# flash.net
KiCad netlist of a schematic drawn in EasyEDA Pro
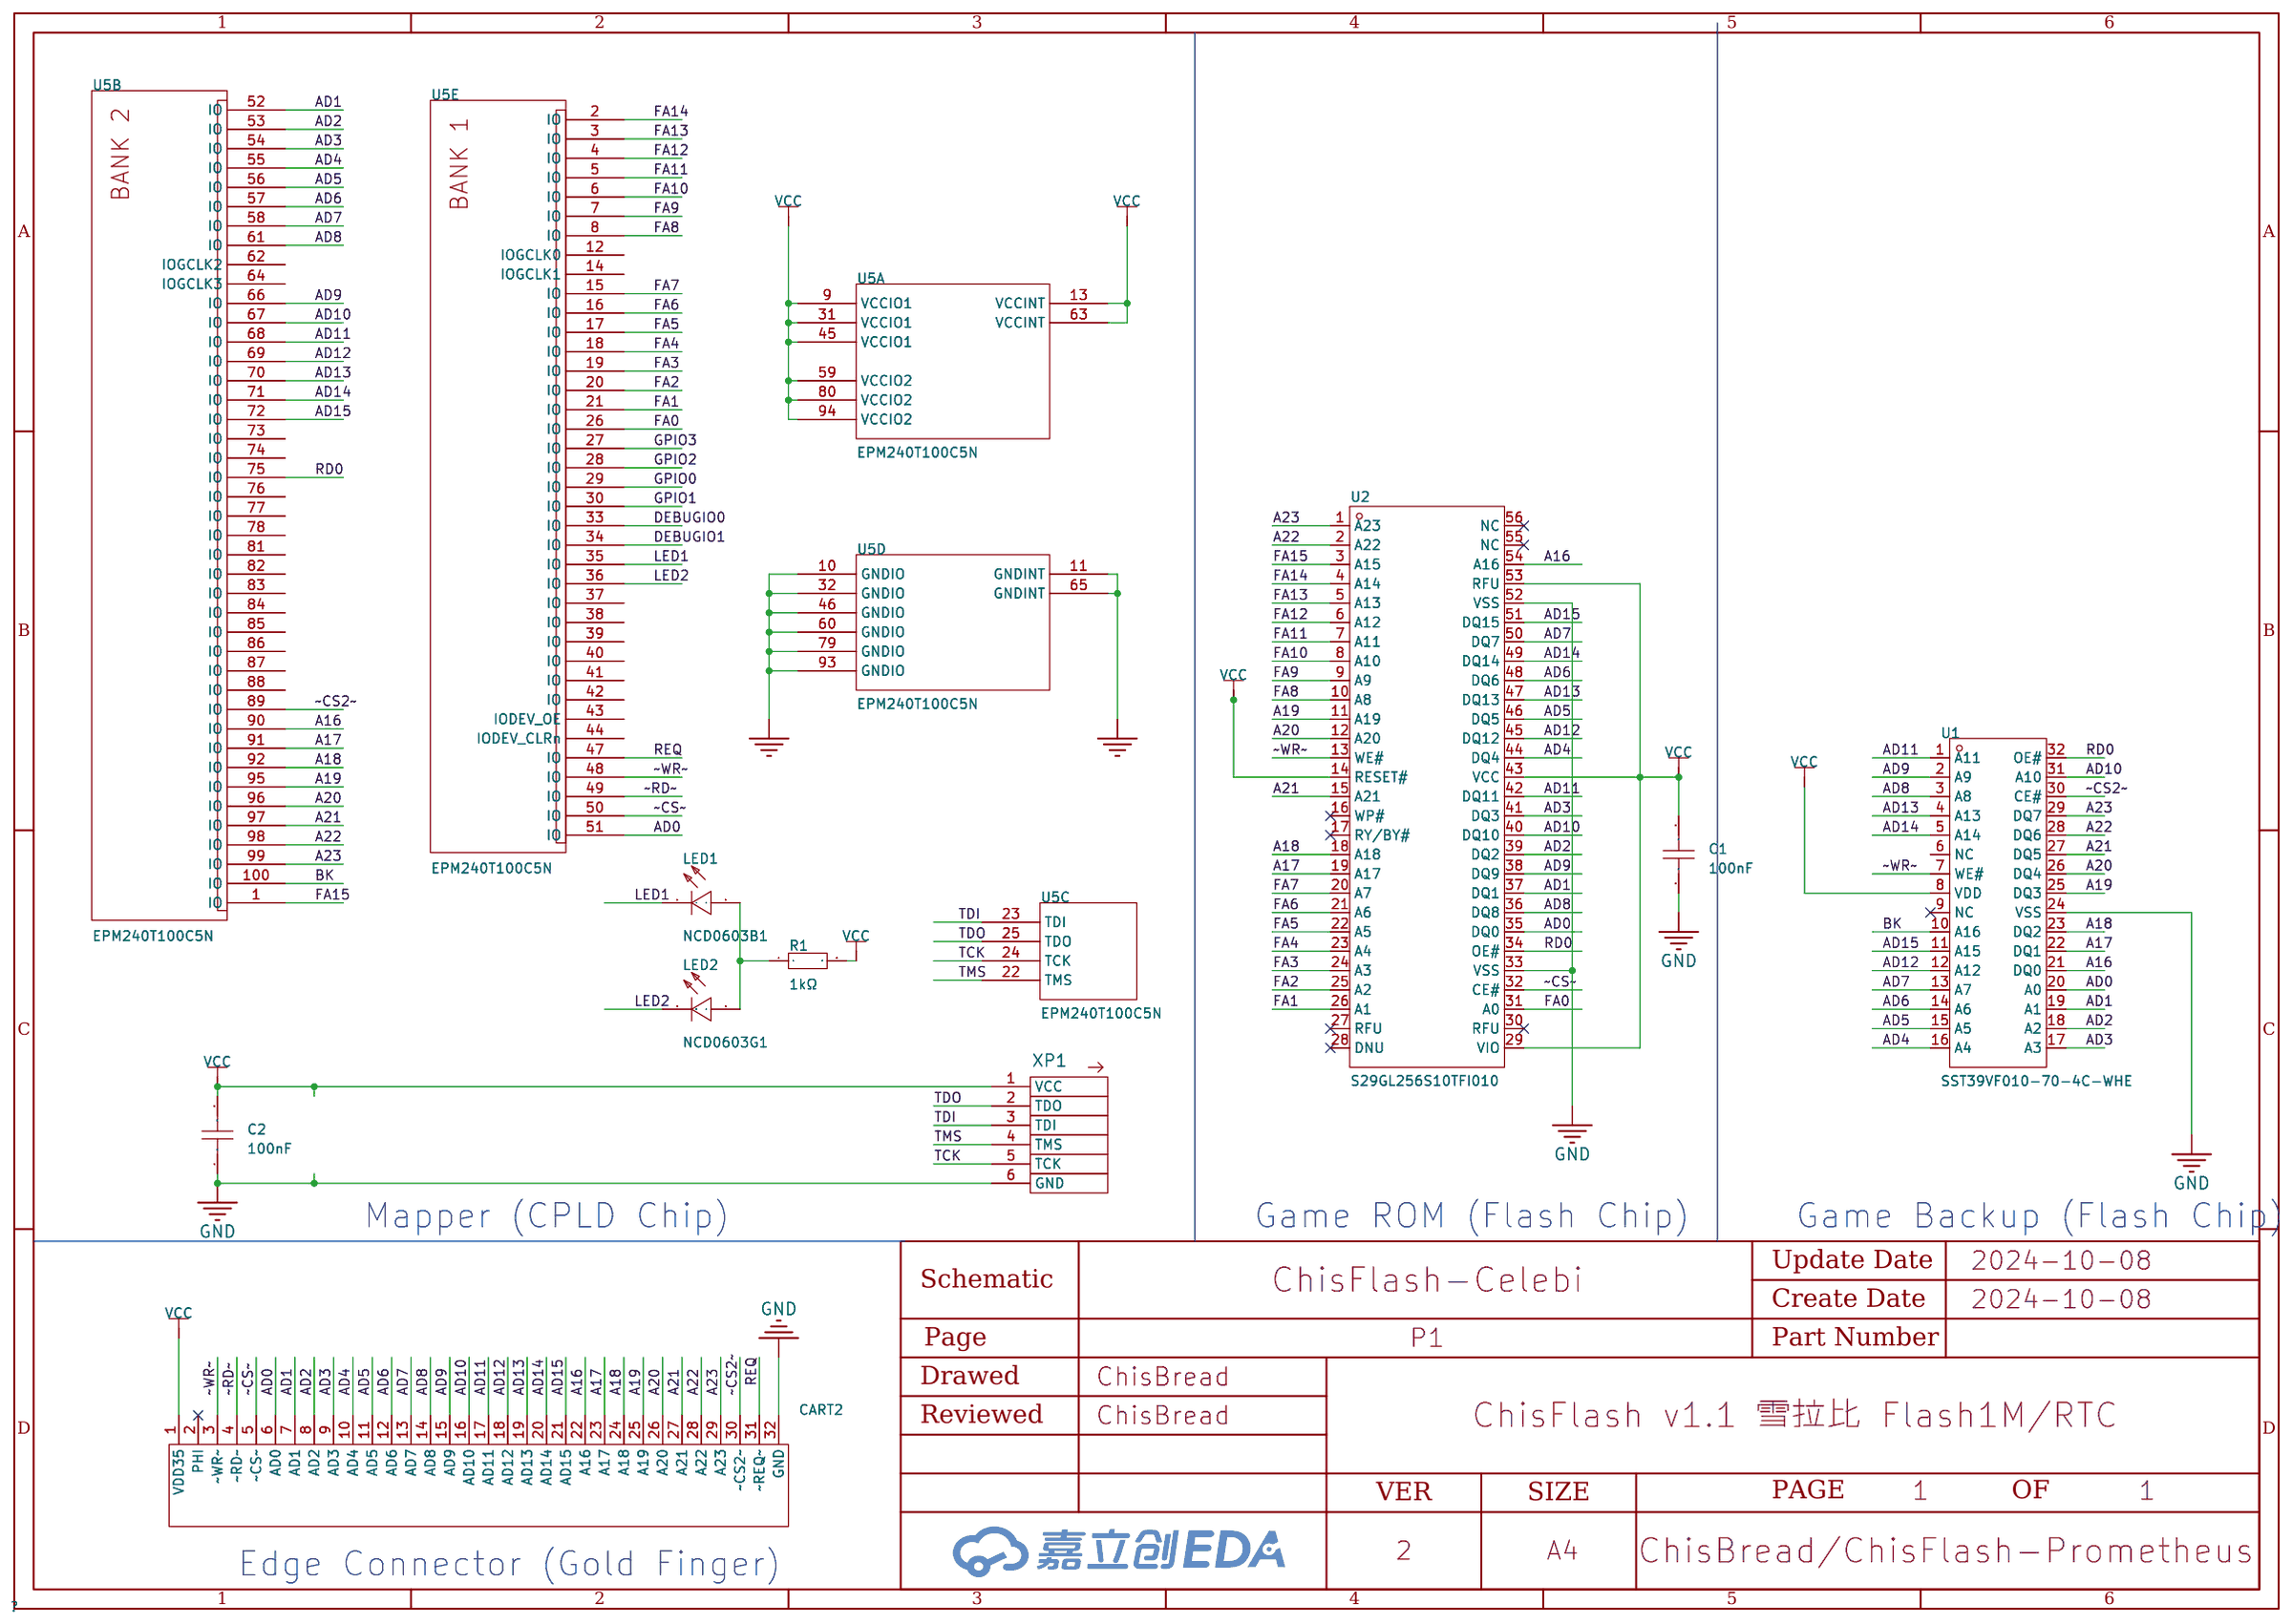
[diagram p0: schematic sheet]

(export (version "E")
  (design (tool "Eeschema 10.0.6"))
  (components
    (comp (ref "C1")
      (value "100nF")
      (footprint "easyedapro:C0603")
      (libsource (lib "easyedapro") (part "CapAcitance"))
    )
    (comp (ref "C2")
      (value "100nF")
      (footprint "easyedapro:C0603")
      (libsource (lib "easyedapro") (part "CapAcitance"))
    )
    (comp (ref "CART2")
      (value "~")
      (footprint "easyedapro:GBA卡带金手指")
      (description "GBA卡带金手指")
      (libsource (lib "easyedapro") (part "GBA卡带金手指"))
    )
    (comp (ref "LED1")
      (value "NCD0603B1")
      (footprint "easyedapro:LED0603-RD")
      (fields (field (name "Manufacturer") "国星光电"))
      (libsource (lib "easyedapro") (part "FC-DA1608BK-470H10"))
    )
    (comp (ref "LED2")
      (value "NCD0603G1")
      (footprint "easyedapro:LED0603-RD")
      (fields (field (name "Manufacturer") "国星光电"))
      (libsource (lib "easyedapro") (part "FC-D1608UGK-520D10"))
    )
    (comp (ref "R1")
      (value "1kΩ")
      (footprint "easyedapro:R0603")
      (description "电阻类型:厚膜电阻;阻值:1kΩ;精度:±1%;功率:100mW;最大工作电压:75V;温度系数:±100ppm/°C;")
      (fields
        (field (name "Manufacturer Part") "0603WAF1001T5E")
        (field (name "Manufacturer") "UNI-ROYAL(厚声)")
      )
      (libsource (lib "easyedapro") (part "0603WAF1001T5E"))
    )
    (comp (ref "U1")
      (value "SST39VF010-70-4C-WHE")
      (footprint "easyedapro:TSOP-32_L8.1-W12.5-P0.50-LS14.2-TL")
      (fields (field (name "Manufacturer") "MICROCHIP(美国微芯)"))
      (libsource (lib "easyedapro") (part "SST39VF010-70-4C-WHE"))
    )
    (comp (ref "U2")
      (value "S29GL256S10TFI010")
      (footprint "easyedapro:TSOP-56_L18.4-W14.0-P0.50-LS20.0-TL")
      (fields (field (name "Manufacturer") "SPANSION(飞索)"))
      (libsource (lib "easyedapro") (part "S29GL256S10TFI010"))
    )
    (comp (ref "U5")
      (value "EPM240T100C5N")
      (footprint "easyedapro:TQFP-100_L14.0-W14.0-P0.50-LS16.0-BL")
      (description "类型:其它PLD;逻辑门数量:-;逻辑单元数:-;逻辑阵列块数:240;")
      (fields (field (name "Manufacturer") "Intel/Altera"))
      (libsource (lib "easyedapro") (part "EPM240T100C5N"))
    )
    (comp (ref "XP1")
      (value "JTAG")
      (footprint "easyedapro:HDR-TH_6P-P1.27-V-M-1")
      (libsource (lib "easyedapro") (part "jtag"))
    )
  )
  (nets
    (net (code "1") (name "/A16") (class "Default")
      (node (ref "CART2") (pin "22") (pinfunction "A16_22") (pintype "input"))
      (node (ref "U1") (pin "21") (pinfunction "DQ0_21") (pintype "unspecified"))
      (node (ref "U2") (pin "54") (pinfunction "A16_54") (pintype "input"))
      (node (ref "U5") (pin "90") (pinfunction "IO_90") (pintype "bidirectional"))
    )
    (net (code "2") (name "/A17") (class "Default")
      (node (ref "CART2") (pin "23") (pinfunction "A17_23") (pintype "input"))
      (node (ref "U1") (pin "22") (pinfunction "DQ1_22") (pintype "unspecified"))
      (node (ref "U2") (pin "19") (pinfunction "A17_19") (pintype "input"))
      (node (ref "U5") (pin "91") (pinfunction "IO_91") (pintype "bidirectional"))
    )
    (net (code "3") (name "/A18") (class "Default")
      (node (ref "CART2") (pin "24") (pinfunction "A18_24") (pintype "input"))
      (node (ref "U1") (pin "23") (pinfunction "DQ2_23") (pintype "unspecified"))
      (node (ref "U2") (pin "18") (pinfunction "A18_18") (pintype "input"))
      (node (ref "U5") (pin "92") (pinfunction "IO_92") (pintype "bidirectional"))
    )
    (net (code "4") (name "/A19") (class "Default")
      (node (ref "CART2") (pin "25") (pinfunction "A19_25") (pintype "input"))
      (node (ref "U1") (pin "25") (pinfunction "DQ3_25") (pintype "unspecified"))
      (node (ref "U2") (pin "11") (pinfunction "A19_11") (pintype "input"))
      (node (ref "U5") (pin "95") (pinfunction "IO_95") (pintype "bidirectional"))
    )
    (net (code "5") (name "/A20") (class "Default")
      (node (ref "CART2") (pin "26") (pinfunction "A20_26") (pintype "input"))
      (node (ref "U1") (pin "26") (pinfunction "DQ4_26") (pintype "unspecified"))
      (node (ref "U2") (pin "12") (pinfunction "A20_12") (pintype "input"))
      (node (ref "U5") (pin "96") (pinfunction "IO_96") (pintype "bidirectional"))
    )
    (net (code "6") (name "/A21") (class "Default")
      (node (ref "CART2") (pin "27") (pinfunction "A21_27") (pintype "input"))
      (node (ref "U1") (pin "27") (pinfunction "DQ5_27") (pintype "unspecified"))
      (node (ref "U2") (pin "15") (pinfunction "A21_15") (pintype "input"))
      (node (ref "U5") (pin "97") (pinfunction "IO_97") (pintype "bidirectional"))
    )
    (net (code "7") (name "/A22") (class "Default")
      (node (ref "CART2") (pin "28") (pinfunction "A22_28") (pintype "input"))
      (node (ref "U1") (pin "28") (pinfunction "DQ6_28") (pintype "unspecified"))
      (node (ref "U2") (pin "2") (pinfunction "A22_2") (pintype "input"))
      (node (ref "U5") (pin "98") (pinfunction "IO_98") (pintype "bidirectional"))
    )
    (net (code "8") (name "/A23") (class "Default")
      (node (ref "CART2") (pin "29") (pinfunction "A23_29") (pintype "input"))
      (node (ref "U1") (pin "29") (pinfunction "DQ7_29") (pintype "unspecified"))
      (node (ref "U2") (pin "1") (pinfunction "A23_1") (pintype "input"))
      (node (ref "U5") (pin "99") (pinfunction "IO_99") (pintype "bidirectional"))
    )
    (net (code "9") (name "/AD0") (class "Default")
      (node (ref "CART2") (pin "6") (pinfunction "AD0_6") (pintype "input"))
      (node (ref "U1") (pin "20") (pinfunction "A0_20") (pintype "unspecified"))
      (node (ref "U2") (pin "35") (pinfunction "DQ0_35") (pintype "input"))
      (node (ref "U5") (pin "51") (pinfunction "IO_51") (pintype "bidirectional"))
    )
    (net (code "10") (name "/AD1") (class "Default")
      (node (ref "CART2") (pin "7") (pinfunction "AD1_7") (pintype "input"))
      (node (ref "U1") (pin "19") (pinfunction "A1_19") (pintype "unspecified"))
      (node (ref "U2") (pin "37") (pinfunction "DQ1_37") (pintype "input"))
      (node (ref "U5") (pin "52") (pinfunction "IO_52") (pintype "bidirectional"))
    )
    (net (code "11") (name "/AD2") (class "Default")
      (node (ref "CART2") (pin "8") (pinfunction "AD2_8") (pintype "input"))
      (node (ref "U1") (pin "18") (pinfunction "A2_18") (pintype "unspecified"))
      (node (ref "U2") (pin "39") (pinfunction "DQ2_39") (pintype "input"))
      (node (ref "U5") (pin "53") (pinfunction "IO_53") (pintype "bidirectional"))
    )
    (net (code "12") (name "/AD3") (class "Default")
      (node (ref "CART2") (pin "9") (pinfunction "AD3_9") (pintype "input"))
      (node (ref "U1") (pin "17") (pinfunction "A3_17") (pintype "unspecified"))
      (node (ref "U2") (pin "41") (pinfunction "DQ3_41") (pintype "input"))
      (node (ref "U5") (pin "54") (pinfunction "IO_54") (pintype "bidirectional"))
    )
    (net (code "13") (name "/AD4") (class "Default")
      (node (ref "CART2") (pin "10") (pinfunction "AD4_10") (pintype "input"))
      (node (ref "U1") (pin "16") (pinfunction "A4_16") (pintype "unspecified"))
      (node (ref "U2") (pin "44") (pinfunction "DQ4_44") (pintype "input"))
      (node (ref "U5") (pin "55") (pinfunction "IO_55") (pintype "bidirectional"))
    )
    (net (code "14") (name "/AD5") (class "Default")
      (node (ref "CART2") (pin "11") (pinfunction "AD5_11") (pintype "input"))
      (node (ref "U1") (pin "15") (pinfunction "A5_15") (pintype "unspecified"))
      (node (ref "U2") (pin "46") (pinfunction "DQ5_46") (pintype "input"))
      (node (ref "U5") (pin "56") (pinfunction "IO_56") (pintype "bidirectional"))
    )
    (net (code "15") (name "/AD6") (class "Default")
      (node (ref "CART2") (pin "12") (pinfunction "AD6_12") (pintype "input"))
      (node (ref "U1") (pin "14") (pinfunction "A6_14") (pintype "unspecified"))
      (node (ref "U2") (pin "48") (pinfunction "DQ6_48") (pintype "input"))
      (node (ref "U5") (pin "57") (pinfunction "IO_57") (pintype "bidirectional"))
    )
    (net (code "16") (name "/AD7") (class "Default")
      (node (ref "CART2") (pin "13") (pinfunction "AD7_13") (pintype "input"))
      (node (ref "U1") (pin "13") (pinfunction "A7_13") (pintype "unspecified"))
      (node (ref "U2") (pin "50") (pinfunction "DQ7_50") (pintype "input"))
      (node (ref "U5") (pin "58") (pinfunction "IO_58") (pintype "bidirectional"))
    )
    (net (code "17") (name "/AD8") (class "Default")
      (node (ref "CART2") (pin "14") (pinfunction "AD8_14") (pintype "input"))
      (node (ref "U1") (pin "3") (pinfunction "A8_3") (pintype "unspecified"))
      (node (ref "U2") (pin "36") (pinfunction "DQ8_36") (pintype "input"))
      (node (ref "U5") (pin "61") (pinfunction "IO_61") (pintype "bidirectional"))
    )
    (net (code "18") (name "/AD9") (class "Default")
      (node (ref "CART2") (pin "15") (pinfunction "AD9_15") (pintype "input"))
      (node (ref "U1") (pin "2") (pinfunction "A9_2") (pintype "unspecified"))
      (node (ref "U2") (pin "38") (pinfunction "DQ9_38") (pintype "input"))
      (node (ref "U5") (pin "66") (pinfunction "IO_66") (pintype "bidirectional"))
    )
    (net (code "19") (name "/AD10") (class "Default")
      (node (ref "CART2") (pin "16") (pinfunction "AD10_16") (pintype "input"))
      (node (ref "U1") (pin "31") (pinfunction "A10_31") (pintype "unspecified"))
      (node (ref "U2") (pin "40") (pinfunction "DQ10_40") (pintype "input"))
      (node (ref "U5") (pin "67") (pinfunction "IO_67") (pintype "bidirectional"))
    )
    (net (code "20") (name "/AD11") (class "Default")
      (node (ref "CART2") (pin "17") (pinfunction "AD11_17") (pintype "input"))
      (node (ref "U1") (pin "1") (pinfunction "A11_1") (pintype "unspecified"))
      (node (ref "U2") (pin "42") (pinfunction "DQ11_42") (pintype "input"))
      (node (ref "U5") (pin "68") (pinfunction "IO_68") (pintype "bidirectional"))
    )
    (net (code "21") (name "/AD12") (class "Default")
      (node (ref "CART2") (pin "18") (pinfunction "AD12_18") (pintype "input"))
      (node (ref "U1") (pin "12") (pinfunction "A12_12") (pintype "unspecified"))
      (node (ref "U2") (pin "45") (pinfunction "DQ12_45") (pintype "input"))
      (node (ref "U5") (pin "69") (pinfunction "IO_69") (pintype "bidirectional"))
    )
    (net (code "22") (name "/AD13") (class "Default")
      (node (ref "CART2") (pin "19") (pinfunction "AD13_19") (pintype "input"))
      (node (ref "U1") (pin "4") (pinfunction "A13_4") (pintype "unspecified"))
      (node (ref "U2") (pin "47") (pinfunction "DQ13_47") (pintype "input"))
      (node (ref "U5") (pin "70") (pinfunction "IO_70") (pintype "bidirectional"))
    )
    (net (code "23") (name "/AD14") (class "Default")
      (node (ref "CART2") (pin "20") (pinfunction "AD14_20") (pintype "input"))
      (node (ref "U1") (pin "5") (pinfunction "A14_5") (pintype "unspecified"))
      (node (ref "U2") (pin "49") (pinfunction "DQ14_49") (pintype "input"))
      (node (ref "U5") (pin "71") (pinfunction "IO_71") (pintype "bidirectional"))
    )
    (net (code "24") (name "/AD15") (class "Default")
      (node (ref "CART2") (pin "21") (pinfunction "AD15_21") (pintype "input"))
      (node (ref "U1") (pin "11") (pinfunction "A15_11") (pintype "unspecified"))
      (node (ref "U2") (pin "51") (pinfunction "DQ15_51") (pintype "input"))
      (node (ref "U5") (pin "72") (pinfunction "IO_72") (pintype "bidirectional"))
    )
    (net (code "25") (name "/BK") (class "Default")
      (node (ref "U1") (pin "10") (pinfunction "A16_10") (pintype "unspecified"))
      (node (ref "U5") (pin "100") (pinfunction "IO_100") (pintype "bidirectional"))
    )
    (net (code "26") (name "/DEBUGIO0") (class "Default")
      (node (ref "U5") (pin "33") (pinfunction "IO_33") (pintype "bidirectional"))
    )
    (net (code "27") (name "/DEBUGIO1") (class "Default")
      (node (ref "U5") (pin "34") (pinfunction "IO_34") (pintype "bidirectional"))
    )
    (net (code "28") (name "/FA0") (class "Default")
      (node (ref "U2") (pin "31") (pinfunction "A0_31") (pintype "input"))
      (node (ref "U5") (pin "26") (pinfunction "IO_26") (pintype "bidirectional"))
    )
    (net (code "29") (name "/FA1") (class "Default")
      (node (ref "U2") (pin "26") (pinfunction "A1_26") (pintype "input"))
      (node (ref "U5") (pin "21") (pinfunction "IO_21") (pintype "bidirectional"))
    )
    (net (code "30") (name "/FA2") (class "Default")
      (node (ref "U2") (pin "25") (pinfunction "A2_25") (pintype "input"))
      (node (ref "U5") (pin "20") (pinfunction "IO_20") (pintype "bidirectional"))
    )
    (net (code "31") (name "/FA3") (class "Default")
      (node (ref "U2") (pin "24") (pinfunction "A3_24") (pintype "input"))
      (node (ref "U5") (pin "19") (pinfunction "IO_19") (pintype "bidirectional"))
    )
    (net (code "32") (name "/FA4") (class "Default")
      (node (ref "U2") (pin "23") (pinfunction "A4_23") (pintype "input"))
      (node (ref "U5") (pin "18") (pinfunction "IO_18") (pintype "bidirectional"))
    )
    (net (code "33") (name "/FA5") (class "Default")
      (node (ref "U2") (pin "22") (pinfunction "A5_22") (pintype "input"))
      (node (ref "U5") (pin "17") (pinfunction "IO_17") (pintype "bidirectional"))
    )
    (net (code "34") (name "/FA6") (class "Default")
      (node (ref "U2") (pin "21") (pinfunction "A6_21") (pintype "input"))
      (node (ref "U5") (pin "16") (pinfunction "IO_16") (pintype "bidirectional"))
    )
    (net (code "35") (name "/FA7") (class "Default")
      (node (ref "U2") (pin "20") (pinfunction "A7_20") (pintype "input"))
      (node (ref "U5") (pin "15") (pinfunction "IO_15") (pintype "bidirectional"))
    )
    (net (code "36") (name "/FA8") (class "Default")
      (node (ref "U2") (pin "10") (pinfunction "A8_10") (pintype "input"))
      (node (ref "U5") (pin "8") (pinfunction "IO_8") (pintype "bidirectional"))
    )
    (net (code "37") (name "/FA9") (class "Default")
      (node (ref "U2") (pin "9") (pinfunction "A9_9") (pintype "input"))
      (node (ref "U5") (pin "7") (pinfunction "IO_7") (pintype "bidirectional"))
    )
    (net (code "38") (name "/FA10") (class "Default")
      (node (ref "U2") (pin "8") (pinfunction "A10_8") (pintype "input"))
      (node (ref "U5") (pin "6") (pinfunction "IO_6") (pintype "bidirectional"))
    )
    (net (code "39") (name "/FA11") (class "Default")
      (node (ref "U2") (pin "7") (pinfunction "A11_7") (pintype "input"))
      (node (ref "U5") (pin "5") (pinfunction "IO_5") (pintype "bidirectional"))
    )
    (net (code "40") (name "/FA12") (class "Default")
      (node (ref "U2") (pin "6") (pinfunction "A12_6") (pintype "input"))
      (node (ref "U5") (pin "4") (pinfunction "IO_4") (pintype "bidirectional"))
    )
    (net (code "41") (name "/FA13") (class "Default")
      (node (ref "U2") (pin "5") (pinfunction "A13_5") (pintype "input"))
      (node (ref "U5") (pin "3") (pinfunction "IO_3") (pintype "bidirectional"))
    )
    (net (code "42") (name "/FA14") (class "Default")
      (node (ref "U2") (pin "4") (pinfunction "A14_4") (pintype "input"))
      (node (ref "U5") (pin "2") (pinfunction "IO_2") (pintype "bidirectional"))
    )
    (net (code "43") (name "/FA15") (class "Default")
      (node (ref "U2") (pin "3") (pinfunction "A15_3") (pintype "input"))
      (node (ref "U5") (pin "1") (pinfunction "IO_1") (pintype "bidirectional"))
    )
    (net (code "44") (name "/GPIO0") (class "Default")
      (node (ref "U5") (pin "29") (pinfunction "IO_29") (pintype "bidirectional"))
    )
    (net (code "45") (name "/GPIO1") (class "Default")
      (node (ref "U5") (pin "30") (pinfunction "IO_30") (pintype "bidirectional"))
    )
    (net (code "46") (name "/GPIO2") (class "Default")
      (node (ref "U5") (pin "28") (pinfunction "IO_28") (pintype "bidirectional"))
    )
    (net (code "47") (name "/GPIO3") (class "Default")
      (node (ref "U5") (pin "27") (pinfunction "IO_27") (pintype "bidirectional"))
    )
    (net (code "48") (name "/LED1") (class "Default")
      (node (ref "LED1") (pin "1") (pinfunction "-_1") (pintype "input"))
      (node (ref "U5") (pin "35") (pinfunction "IO_35") (pintype "bidirectional"))
    )
    (net (code "49") (name "/LED2") (class "Default")
      (node (ref "LED2") (pin "1") (pinfunction "K_1") (pintype "input"))
      (node (ref "U5") (pin "36") (pinfunction "IO_36") (pintype "bidirectional"))
    )
    (net (code "50") (name "/RD0") (class "Default")
      (node (ref "U1") (pin "32") (pinfunction "OE#_32") (pintype "unspecified"))
      (node (ref "U2") (pin "34") (pinfunction "OE#_34") (pintype "input"))
      (node (ref "U5") (pin "75") (pinfunction "IO_75") (pintype "bidirectional"))
    )
    (net (code "51") (name "/REQ") (class "Default")
      (node (ref "CART2") (pin "31") (pinfunction "~REQ~_31") (pintype "input"))
      (node (ref "U5") (pin "47") (pinfunction "IO_47") (pintype "bidirectional"))
    )
    (net (code "52") (name "/TCK") (class "Default")
      (node (ref "U5") (pin "24") (pinfunction "TCK_24") (pintype "unspecified"))
      (node (ref "XP1") (pin "5") (pinfunction "TCK_5") (pintype "input"))
    )
    (net (code "53") (name "/TDI") (class "Default")
      (node (ref "U5") (pin "23") (pinfunction "TDI_23") (pintype "unspecified"))
      (node (ref "XP1") (pin "3") (pinfunction "TDI_3") (pintype "output"))
    )
    (net (code "54") (name "/TDO") (class "Default")
      (node (ref "U5") (pin "25") (pinfunction "TDO_25") (pintype "output"))
      (node (ref "XP1") (pin "2") (pinfunction "TDO_2") (pintype "output"))
    )
    (net (code "55") (name "/TMS") (class "Default")
      (node (ref "U5") (pin "22") (pinfunction "TMS_22") (pintype "unspecified"))
      (node (ref "XP1") (pin "4") (pinfunction "TMS_4") (pintype "output"))
    )
    (net (code "56") (name "/~CS2~") (class "Default")
      (node (ref "CART2") (pin "30") (pinfunction "~CS2~_30") (pintype "input"))
      (node (ref "U1") (pin "30") (pinfunction "CE#_30") (pintype "unspecified"))
      (node (ref "U5") (pin "89") (pinfunction "IO_89") (pintype "bidirectional"))
    )
    (net (code "57") (name "/~CS~") (class "Default")
      (node (ref "CART2") (pin "5") (pinfunction "~CS~_5") (pintype "input"))
      (node (ref "U2") (pin "32") (pinfunction "CE#_32") (pintype "input"))
      (node (ref "U5") (pin "50") (pinfunction "IO_50") (pintype "bidirectional"))
    )
    (net (code "58") (name "/~RD~") (class "Default")
      (node (ref "CART2") (pin "4") (pinfunction "~RD~_4") (pintype "input"))
      (node (ref "U5") (pin "49") (pinfunction "IO_49") (pintype "bidirectional"))
    )
    (net (code "59") (name "/~WR~") (class "Default")
      (node (ref "CART2") (pin "3") (pinfunction "~WR~_3") (pintype "input"))
      (node (ref "U1") (pin "7") (pinfunction "WE#_7") (pintype "unspecified"))
      (node (ref "U2") (pin "13") (pinfunction "WE#_13") (pintype "input"))
      (node (ref "U5") (pin "48") (pinfunction "IO_48") (pintype "bidirectional"))
    )
    (net (code "60") (name "GND") (class "Default")
      (node (ref "C1") (pin "1") (pinfunction "1_1") (pintype "input"))
      (node (ref "C2") (pin "1") (pinfunction "1_1") (pintype "input"))
      (node (ref "CART2") (pin "32") (pinfunction "GND_32") (pintype "input"))
      (node (ref "U1") (pin "24") (pinfunction "VSS_24") (pintype "unspecified"))
      (node (ref "U2") (pin "33") (pinfunction "VSS_33") (pintype "input"))
      (node (ref "U2") (pin "52") (pinfunction "VSS_52") (pintype "input"))
      (node (ref "U5") (pin "10") (pinfunction "GNDIO_10") (pintype "unspecified"))
      (node (ref "U5") (pin "11") (pinfunction "GNDINT_11") (pintype "unspecified"))
      (node (ref "U5") (pin "32") (pinfunction "GNDIO_32") (pintype "unspecified"))
      (node (ref "U5") (pin "46") (pinfunction "GNDIO_46") (pintype "unspecified"))
      (node (ref "U5") (pin "60") (pinfunction "GNDIO_60") (pintype "unspecified"))
      (node (ref "U5") (pin "65") (pinfunction "GNDINT_65") (pintype "unspecified"))
      (node (ref "U5") (pin "79") (pinfunction "GNDIO_79") (pintype "unspecified"))
      (node (ref "U5") (pin "93") (pinfunction "GNDIO_93") (pintype "unspecified"))
      (node (ref "XP1") (pin "6") (pinfunction "GND_6") (pintype "input"))
    )
    (net (code "61") (name "Net-(LED1-+)") (class "Default")
      (node (ref "LED1") (pin "2") (pinfunction "+_2") (pintype "input"))
      (node (ref "LED2") (pin "2") (pinfunction "A_2") (pintype "input"))
      (node (ref "R1") (pin "1") (pinfunction "1_1") (pintype "input"))
    )
    (net (code "62") (name "VCC") (class "Default")
      (node (ref "C1") (pin "2") (pinfunction "2_2") (pintype "input"))
      (node (ref "C2") (pin "2") (pinfunction "2_2") (pintype "input"))
      (node (ref "CART2") (pin "1") (pinfunction "VDD35_1") (pintype "input"))
      (node (ref "R1") (pin "2") (pinfunction "2_2") (pintype "input"))
      (node (ref "U1") (pin "8") (pinfunction "VDD_8") (pintype "unspecified"))
      (node (ref "U2") (pin "14") (pinfunction "RESET#_14") (pintype "input"))
      (node (ref "U2") (pin "29") (pinfunction "VIO_29") (pintype "input"))
      (node (ref "U2") (pin "43") (pinfunction "VCC_43") (pintype "input"))
      (node (ref "U2") (pin "53") (pinfunction "RFU_53") (pintype "input"))
      (node (ref "U5") (pin "13") (pinfunction "VCCINT_13") (pintype "unspecified"))
      (node (ref "U5") (pin "31") (pinfunction "VCCIO1_31") (pintype "unspecified"))
      (node (ref "U5") (pin "45") (pinfunction "VCCIO1_45") (pintype "unspecified"))
      (node (ref "U5") (pin "59") (pinfunction "VCCIO2_59") (pintype "unspecified"))
      (node (ref "U5") (pin "63") (pinfunction "VCCINT_63") (pintype "unspecified"))
      (node (ref "U5") (pin "80") (pinfunction "VCCIO2_80") (pintype "unspecified"))
      (node (ref "U5") (pin "9") (pinfunction "VCCIO1_9") (pintype "unspecified"))
      (node (ref "U5") (pin "94") (pinfunction "VCCIO2_94") (pintype "unspecified"))
      (node (ref "XP1") (pin "1") (pinfunction "VCC_1") (pintype "output"))
    )
    (net (code "63") (name "unconnected-(CART2-PHI-Pad2)") (class "Default")
      (node (ref "CART2") (pin "2") (pinfunction "PHI_2") (pintype "input+no_connect"))
    )
    (net (code "64") (name "unconnected-(U1-NC-Pad6)") (class "Default")
      (node (ref "U1") (pin "6") (pinfunction "NC_6") (pintype "unspecified"))
    )
    (net (code "65") (name "unconnected-(U1-NC-Pad9)") (class "Default")
      (node (ref "U1") (pin "9") (pinfunction "NC_9") (pintype "unspecified+no_connect"))
    )
    (net (code "66") (name "unconnected-(U2-DNU-Pad28)") (class "Default")
      (node (ref "U2") (pin "28") (pinfunction "DNU_28") (pintype "input+no_connect"))
    )
    (net (code "67") (name "unconnected-(U2-NC-Pad55)") (class "Default")
      (node (ref "U2") (pin "55") (pinfunction "NC_55") (pintype "input+no_connect"))
    )
    (net (code "68") (name "unconnected-(U2-NC-Pad56)") (class "Default")
      (node (ref "U2") (pin "56") (pinfunction "NC_56") (pintype "input+no_connect"))
    )
    (net (code "69") (name "unconnected-(U2-RFU-Pad27)") (class "Default")
      (node (ref "U2") (pin "27") (pinfunction "RFU_27") (pintype "input+no_connect"))
    )
    (net (code "70") (name "unconnected-(U2-RFU-Pad30)") (class "Default")
      (node (ref "U2") (pin "30") (pinfunction "RFU_30") (pintype "input+no_connect"))
    )
    (net (code "71") (name "unconnected-(U2-RY{slash}BY#-Pad17)") (class "Default")
      (node (ref "U2") (pin "17") (pinfunction "RY/BY#_17") (pintype "input+no_connect"))
    )
    (net (code "72") (name "unconnected-(U2-WP#-Pad16)") (class "Default")
      (node (ref "U2") (pin "16") (pinfunction "WP#_16") (pintype "input+no_connect"))
    )
    (net (code "73") (name "unconnected-(U5B-IO-Pad73)") (class "Default")
      (node (ref "U5") (pin "73") (pinfunction "IO_73") (pintype "bidirectional"))
    )
    (net (code "74") (name "unconnected-(U5B-IO-Pad74)") (class "Default")
      (node (ref "U5") (pin "74") (pinfunction "IO_74") (pintype "bidirectional"))
    )
    (net (code "75") (name "unconnected-(U5B-IO-Pad76)") (class "Default")
      (node (ref "U5") (pin "76") (pinfunction "IO_76") (pintype "bidirectional"))
    )
    (net (code "76") (name "unconnected-(U5B-IO-Pad77)") (class "Default")
      (node (ref "U5") (pin "77") (pinfunction "IO_77") (pintype "bidirectional"))
    )
    (net (code "77") (name "unconnected-(U5B-IO-Pad78)") (class "Default")
      (node (ref "U5") (pin "78") (pinfunction "IO_78") (pintype "bidirectional"))
    )
    (net (code "78") (name "unconnected-(U5B-IO-Pad81)") (class "Default")
      (node (ref "U5") (pin "81") (pinfunction "IO_81") (pintype "bidirectional"))
    )
    (net (code "79") (name "unconnected-(U5B-IO-Pad82)") (class "Default")
      (node (ref "U5") (pin "82") (pinfunction "IO_82") (pintype "bidirectional"))
    )
    (net (code "80") (name "unconnected-(U5B-IO-Pad83)") (class "Default")
      (node (ref "U5") (pin "83") (pinfunction "IO_83") (pintype "bidirectional"))
    )
    (net (code "81") (name "unconnected-(U5B-IO-Pad84)") (class "Default")
      (node (ref "U5") (pin "84") (pinfunction "IO_84") (pintype "bidirectional"))
    )
    (net (code "82") (name "unconnected-(U5B-IO-Pad85)") (class "Default")
      (node (ref "U5") (pin "85") (pinfunction "IO_85") (pintype "bidirectional"))
    )
    (net (code "83") (name "unconnected-(U5B-IO-Pad86)") (class "Default")
      (node (ref "U5") (pin "86") (pinfunction "IO_86") (pintype "bidirectional"))
    )
    (net (code "84") (name "unconnected-(U5B-IO-Pad87)") (class "Default")
      (node (ref "U5") (pin "87") (pinfunction "IO_87") (pintype "bidirectional"))
    )
    (net (code "85") (name "unconnected-(U5B-IO-Pad88)") (class "Default")
      (node (ref "U5") (pin "88") (pinfunction "IO_88") (pintype "bidirectional"))
    )
    (net (code "86") (name "unconnected-(U5B-IOGCLK2-Pad62)") (class "Default")
      (node (ref "U5") (pin "62") (pinfunction "IOGCLK2_62") (pintype "bidirectional"))
    )
    (net (code "87") (name "unconnected-(U5B-IOGCLK3-Pad64)") (class "Default")
      (node (ref "U5") (pin "64") (pinfunction "IOGCLK3_64") (pintype "bidirectional"))
    )
    (net (code "88") (name "unconnected-(U5E-IO-Pad37)") (class "Default")
      (node (ref "U5") (pin "37") (pinfunction "IO_37") (pintype "bidirectional"))
    )
    (net (code "89") (name "unconnected-(U5E-IO-Pad38)") (class "Default")
      (node (ref "U5") (pin "38") (pinfunction "IO_38") (pintype "bidirectional"))
    )
    (net (code "90") (name "unconnected-(U5E-IO-Pad39)") (class "Default")
      (node (ref "U5") (pin "39") (pinfunction "IO_39") (pintype "bidirectional"))
    )
    (net (code "91") (name "unconnected-(U5E-IO-Pad40)") (class "Default")
      (node (ref "U5") (pin "40") (pinfunction "IO_40") (pintype "bidirectional"))
    )
    (net (code "92") (name "unconnected-(U5E-IO-Pad41)") (class "Default")
      (node (ref "U5") (pin "41") (pinfunction "IO_41") (pintype "bidirectional"))
    )
    (net (code "93") (name "unconnected-(U5E-IO-Pad42)") (class "Default")
      (node (ref "U5") (pin "42") (pinfunction "IO_42") (pintype "bidirectional"))
    )
    (net (code "94") (name "unconnected-(U5E-IODEV_CLRn-Pad44)") (class "Default")
      (node (ref "U5") (pin "44") (pinfunction "IODEV_CLRn_44") (pintype "bidirectional"))
    )
    (net (code "95") (name "unconnected-(U5E-IODEV_OE-Pad43)") (class "Default")
      (node (ref "U5") (pin "43") (pinfunction "IODEV_OE_43") (pintype "bidirectional"))
    )
    (net (code "96") (name "unconnected-(U5E-IOGCLK0-Pad12)") (class "Default")
      (node (ref "U5") (pin "12") (pinfunction "IOGCLK0_12") (pintype "bidirectional"))
    )
    (net (code "97") (name "unconnected-(U5E-IOGCLK1-Pad14)") (class "Default")
      (node (ref "U5") (pin "14") (pinfunction "IOGCLK1_14") (pintype "bidirectional"))
    )
  )
)
